# POWER_GATEWAY.net
KiCad netlist of a schematic drawn in Altium Designer
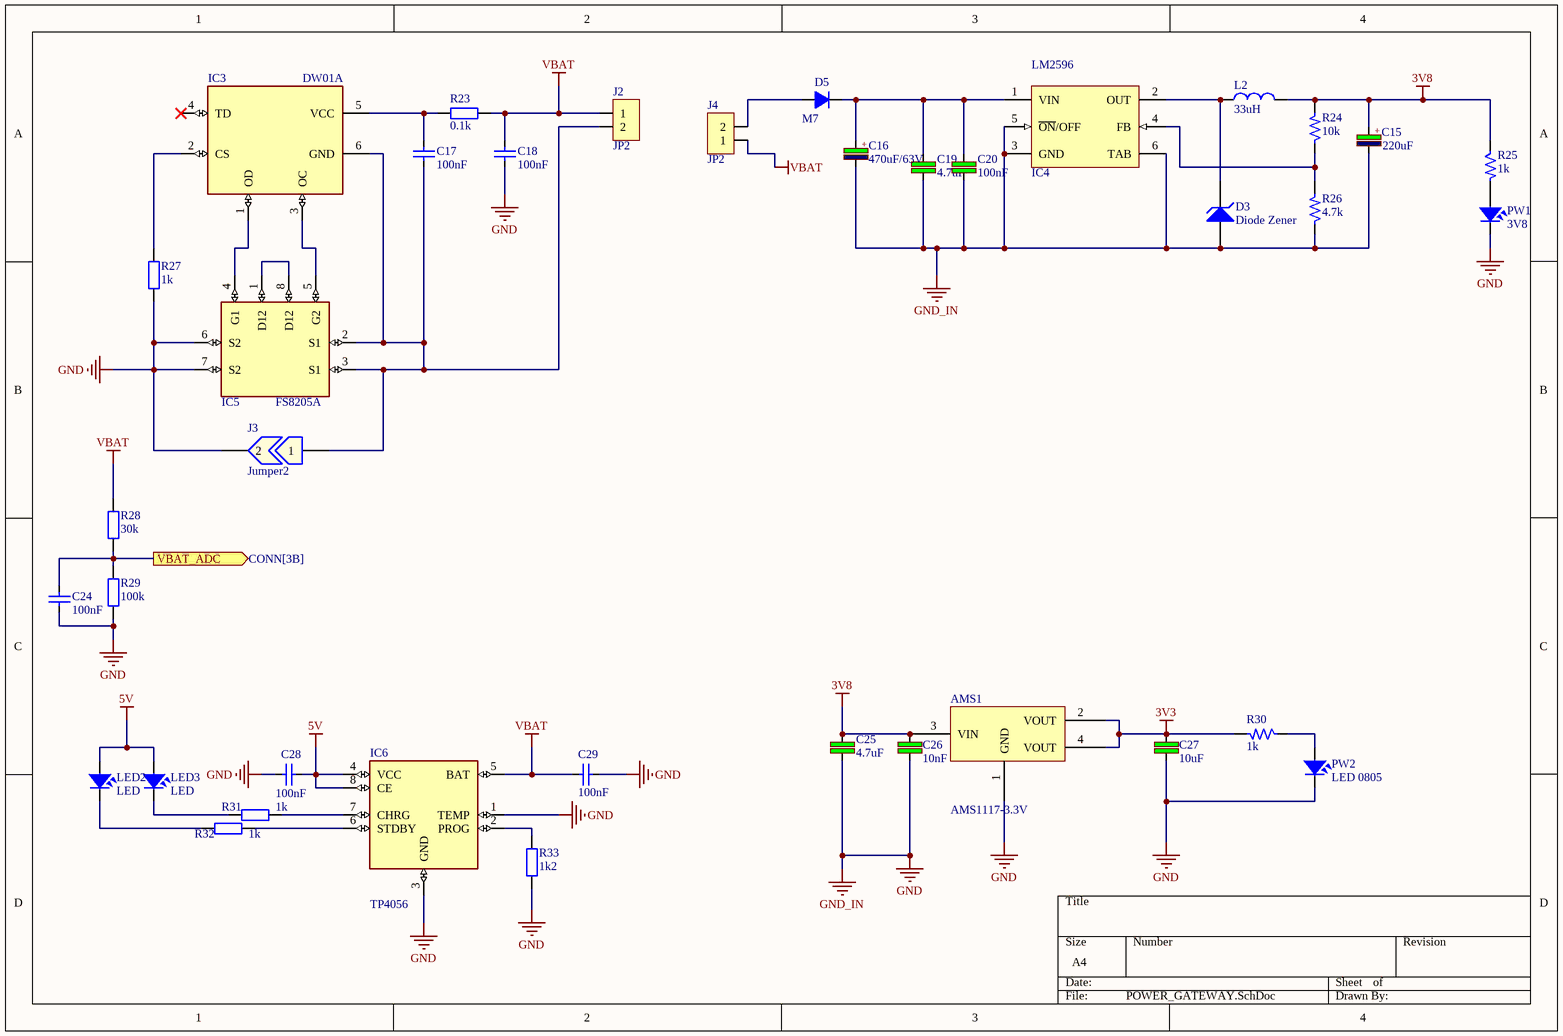
[diagram p0: POWER_GATEWAY.SchDoc]

(export (version "E")
  (design (tool "Eeschema 10.0.6"))
  (components
    (comp (ref "AMS1")
      (value "AMS1117-3.3V")
      (footprint "SOT223")
      (description "Dán")
      (libsource (lib "IC") (part "AMS1117 SMD"))
    )
    (comp (ref "C15")
      (value "220uF")
      (footprint "CAP_TANTALUM_3216")
      (description "220µF Molded Tantalum Polymer Capacitor 16V 2917 (7343 Metric) 40mOhm @ 100kHz")
      (fields
        (field (name "MANUFACTURER") "AVX Corporation")
        (field (name "PART NUMBER") "TCME227M016R0040E")
      )
      (libsource (lib "Anh_Trung") (part "CP5"))
    )
    (comp (ref "C16")
      (value "470uF/63V")
      (footprint "CAP-ALU-SMD-C")
      (description "Cap 470uF/63V")
      (libsource (lib "Main") (part "CP3"))
    )
    (comp (ref "C17")
      (value "100nF")
      (footprint "CAP_0805")
      (description "Capacitor")
      (fields (field (name "PUBLISHER") "Altium Limited"))
      (libsource (lib "My Library") (part "CapSMD"))
    )
    (comp (ref "C18")
      (value "100nF")
      (footprint "CAP_0805")
      (description "Capacitor")
      (fields (field (name "PUBLISHER") "Altium Limited"))
      (libsource (lib "My Library") (part "CapSMD"))
    )
    (comp (ref "C19")
      (value "4.7uF")
      (footprint "C-0805")
      (description "4.7µF ±10% 35V Ceramic Capacitor X5R 0805 (2012 Metric)")
      (fields
        (field (name "MANUFACTURER") "Samsung Electro-Mechanics")
        (field (name "PART NUMBER") "CL21A475KLCLQNC")
      )
      (libsource (lib "Anh_Trung") (part "C"))
    )
    (comp (ref "C20")
      (value "100nF")
      (footprint "C-0805")
      (description "4.7µF ±10% 35V Ceramic Capacitor X5R 0805 (2012 Metric)")
      (fields
        (field (name "MANUFACTURER") "Samsung Electro-Mechanics")
        (field (name "PART NUMBER") "CL21A475KLCLQNC")
      )
      (libsource (lib "Anh_Trung") (part "C"))
    )
    (comp (ref "C24")
      (value "100nF")
      (footprint "CAP_0805")
      (description "Capacitor")
      (fields (field (name "PUBLISHER") "Altium Limited"))
      (libsource (lib "My Library") (part "CapSMD"))
    )
    (comp (ref "C25")
      (value "4.7uF")
      (footprint "C-0805")
      (description "4.7µF ±10% 35V Ceramic Capacitor X5R 0805 (2012 Metric)")
      (fields
        (field (name "MANUFACTURER") "Samsung Electro-Mechanics")
        (field (name "PART NUMBER") "CL21A475KLCLQNC")
      )
      (libsource (lib "Anh_Trung") (part "C"))
    )
    (comp (ref "C26")
      (value "10nF")
      (footprint "C-0805")
      (description "Cap SMD")
      (fields
        (field (name "MANUFACTURER") "Samsung Electro-Mechanics")
        (field (name "PART NUMBER") "CL21A106KPFNNNG")
      )
      (libsource (lib "") (part "C_1"))
    )
    (comp (ref "C27")
      (value "10uF")
      (footprint "C-0805")
      (description "Cap SMD")
      (fields
        (field (name "MANUFACTURER") "Samsung Electro-Mechanics")
        (field (name "PART NUMBER") "CL21A106KPFNNNG")
      )
      (libsource (lib "") (part "C_1"))
    )
    (comp (ref "C28")
      (value "100nF")
      (footprint "CAP_0805")
      (description "Capacitor")
      (fields (field (name "PUBLISHER") "Altium Limited"))
      (libsource (lib "My Library") (part "CapSMD"))
    )
    (comp (ref "C29")
      (value "100nF")
      (footprint "CAP_0805")
      (description "Capacitor")
      (fields (field (name "PUBLISHER") "Altium Limited"))
      (libsource (lib "My Library") (part "CapSMD"))
    )
    (comp (ref "D3")
      (value "Diode Zener")
      (footprint "DIODE_ZENER_SMD")
      (description "Zener Diode")
      (fields (field (name "PUBLISHER") "Altium Limited"))
      (libsource (lib "My Library 2") (part "Diode Zener"))
    )
    (comp (ref "D5")
      (value "M7")
      (footprint "SMA")
      (description "Diode 1A")
      (libsource (lib "Main") (part "D1A"))
    )
    (comp (ref "IC3")
      (value "DW01A")
      (footprint "SOT23-6")
      (description "One Cell Lithium-ion/Polymer Battery Protection IC")
      (libsource (lib "My Library") (part "DW01A"))
    )
    (comp (ref "IC4")
      (value "LM2596")
      (footprint "TO-263")
      (description "LM2576")
      (libsource (lib "Main") (part "LM2576"))
    )
    (comp (ref "IC5") (value "FS8205A") (footprint "FS8205A") (libsource (lib "My Library") (part "FS8205A")))
    (comp (ref "IC6")
      (value "TP4056")
      (footprint "TP4056")
      (description "Complete single cell Li-Ion battery with a constant current / constant voltage linear charger")
      (libsource (lib "My Library") (part "TP4056"))
    )
    (comp (ref "J2")
      (value "JP2")
      (footprint "KF2-5.08")
      (description "WR-PHD 2.54 mm Angled Socket Header")
      (fields
        (field (name "MANUFACTURER") "Würth Elektronik eiSos GmbH")
        (field (name "PARTNO") "613002143121")
        (field (name "CREATED BY") "Karrer Zheng")
      )
      (libsource (lib "My Library") (part "JP2"))
    )
    (comp (ref "J3")
      (value "Jumper2")
      (footprint "JUMPER2")
      (description "Jumper, 2-Pin")
      (libsource (lib "My Library") (part "Jumper2"))
    )
    (comp (ref "J4")
      (value "JP2")
      (footprint "KF2-5.08")
      (description "WR-PHD 2.54 mm Angled Socket Header")
      (fields
        (field (name "MANUFACTURER") "Würth Elektronik eiSos GmbH")
        (field (name "PARTNO") "613002143121")
        (field (name "CREATED BY") "Karrer Zheng")
      )
      (libsource (lib "") (part "JP2_1"))
    )
    (comp (ref "L2")
      (value "33uH")
      (footprint "Inductor_SMD")
      (description "22µH Shielded Inductor 1.65A 96mOhm Max Nonstandard")
      (fields (field (name "MANUFACTURER") "Bourns Inc.") (field (name "PART NUMBER") "SRR0745A-220M"))
      (libsource (lib "Main") (part "L1"))
    )
    (comp (ref "LED2")
      (value "LED")
      (footprint "LED-0805-Blue")
      (description "LED Single colour Green and Red")
      (libsource (lib "My Library") (part "LED"))
    )
    (comp (ref "LED3")
      (value "LED")
      (footprint "LED-0805-Blue")
      (description "LED Single colour Green and Red")
      (libsource (lib "My Library") (part "LED"))
    )
    (comp (ref "PW1")
      (value "3V8")
      (footprint "LED-0805-Blue")
      (description "LED RED DIFFUSED 0805 SMD")
      (fields
        (field (name "MANUFACTURER") "OSRAM Opto Semiconductors Inc.")
        (field (name "PART NUMBER") "LS R976-NR-1")
      )
      (libsource (lib "Anh_Trung") (part "LED"))
    )
    (comp (ref "PW2")
      (value "LED 0805")
      (footprint "LED-0805-Blue")
      (description "LED RED DIFFUSED 0805 SMD")
      (fields
        (field (name "MANUFACTURER") "OSRAM Opto Semiconductors Inc.")
        (field (name "PART NUMBER") "LS R976-NR-1")
      )
      (libsource (lib "Main") (part "LED"))
    )
    (comp (ref "R23")
      (value "0.1k")
      (footprint "RES-SMD-0805")
      (description "Resistor SMD")
      (fields
        (field (name "MANUFACTURER") "Generic Components")
        (field (name "PUBLISHER") "Altium Hobart Technology Centre")
      )
      (libsource (lib "My Library") (part "Resistor - SMD"))
    )
    (comp (ref "R24")
      (value "10k")
      (footprint "R-0805")
      (description "RES SMD 10K OHM 1% 1/8W 0805")
      (fields (field (name "MANUFACTURER") "Yageo") (field (name "PART NUMBER") "RC0805FR-0710KL"))
      (libsource (lib "Anh_Trung") (part "R"))
    )
    (comp (ref "R25")
      (value "1k")
      (footprint "R-0805")
      (description "Resistor 1/4W")
      (fields (field (name "MANUFACTURER") "Yageo") (field (name "PART NUMBER") "RC0805FR-071KL"))
      (libsource (lib "Anh_Trung") (part "R"))
    )
    (comp (ref "R26")
      (value "4.7k")
      (footprint "R-0805")
      (description "RES SMD 3.3K OHM 1% 1/8W 0805")
      (fields (field (name "MANUFACTURER") "Yageo") (field (name "PART NUMBER") "RC0805FR-073K3L"))
      (libsource (lib "Anh_Trung") (part "R"))
    )
    (comp (ref "R27")
      (value "1k")
      (footprint "RES-SMD-0805")
      (description "Resistor SMD")
      (fields
        (field (name "MANUFACTURER") "Generic Components")
        (field (name "PUBLISHER") "Altium Hobart Technology Centre")
      )
      (libsource (lib "My Library") (part "Resistor - SMD"))
    )
    (comp (ref "R28")
      (value "30k")
      (footprint "RES-SMD-0805")
      (description "Resistor SMD")
      (fields
        (field (name "MANUFACTURER") "Generic Components")
        (field (name "PUBLISHER") "Altium Hobart Technology Centre")
      )
      (libsource (lib "My Library") (part "Resistor - SMD"))
    )
    (comp (ref "R29")
      (value "100k")
      (footprint "RES-SMD-0805")
      (description "Resistor SMD")
      (fields
        (field (name "MANUFACTURER") "Generic Components")
        (field (name "PUBLISHER") "Altium Hobart Technology Centre")
      )
      (libsource (lib "My Library") (part "Resistor - SMD"))
    )
    (comp (ref "R30")
      (value "1k")
      (footprint "R-0805")
      (description "Resistor 1/4W")
      (fields (field (name "MANUFACTURER") "Yageo") (field (name "PART NUMBER") "RC0805FR-071KL"))
      (libsource (lib "Anh_Trung") (part "R"))
    )
    (comp (ref "R31")
      (value "1k")
      (footprint "RES-SMD-0805")
      (description "Resistor SMD")
      (fields
        (field (name "MANUFACTURER") "Generic Components")
        (field (name "PUBLISHER") "Altium Hobart Technology Centre")
      )
      (libsource (lib "My Library") (part "Resistor - SMD"))
    )
    (comp (ref "R32")
      (value "1k")
      (footprint "RES-SMD-0805")
      (description "Resistor SMD")
      (fields
        (field (name "MANUFACTURER") "Generic Components")
        (field (name "PUBLISHER") "Altium Hobart Technology Centre")
      )
      (libsource (lib "My Library") (part "Resistor - SMD"))
    )
    (comp (ref "R33")
      (value "1k2")
      (footprint "RES-SMD-0805")
      (description "Resistor SMD")
      (fields
        (field (name "MANUFACTURER") "Generic Components")
        (field (name "PUBLISHER") "Altium Hobart Technology Centre")
      )
      (libsource (lib "My Library") (part "Resistor - SMD"))
    )
  )
  (nets
    (net (code "1") (name "/VBAT_ADC") (class "Default")
      (node (ref "C24") (pin "2") (pinfunction "2_2") (pintype "passive"))
      (node (ref "R28") (pin "1") (pinfunction "1_1") (pintype "passive"))
      (node (ref "R29") (pin "2") (pinfunction "2_2") (pintype "passive"))
    )
    (net (code "2") (name "3V3") (class "Default")
      (node (ref "AMS1") (pin "2") (pinfunction "VOUT_2") (pintype "passive"))
      (node (ref "AMS1") (pin "4") (pinfunction "VOUT_4") (pintype "passive"))
      (node (ref "C27") (pin "1") (pinfunction "1_1") (pintype "passive"))
      (node (ref "R30") (pin "2") (pinfunction "2_2") (pintype "passive"))
    )
    (net (code "3") (name "3V8") (class "Default")
      (node (ref "AMS1") (pin "3") (pinfunction "VIN_3") (pintype "passive"))
      (node (ref "C15") (pin "1") (pinfunction "1_1") (pintype "passive"))
      (node (ref "C25") (pin "2") (pinfunction "2_2") (pintype "passive"))
      (node (ref "C26") (pin "1") (pinfunction "1_1") (pintype "passive"))
      (node (ref "L2") (pin "2") (pinfunction "2_2") (pintype "passive"))
      (node (ref "R24") (pin "2") (pinfunction "2_2") (pintype "passive"))
      (node (ref "R25") (pin "1") (pinfunction "1_1") (pintype "passive"))
    )
    (net (code "4") (name "5V") (class "Default")
      (node (ref "C28") (pin "1") (pinfunction "1_1") (pintype "passive"))
      (node (ref "IC6") (pin "4") (pinfunction "VCC_4") (pintype "bidirectional"))
      (node (ref "IC6") (pin "8") (pinfunction "CE_8") (pintype "bidirectional"))
      (node (ref "LED2") (pin "1") (pinfunction "1_1") (pintype "passive"))
      (node (ref "LED3") (pin "1") (pinfunction "1_1") (pintype "passive"))
    )
    (net (code "5") (name "GND") (class "Default")
      (node (ref "AMS1") (pin "1") (pinfunction "GND_1") (pintype "passive"))
      (node (ref "C15") (pin "2") (pinfunction "2_2") (pintype "passive"))
      (node (ref "C16") (pin "2") (pinfunction "2_2") (pintype "passive"))
      (node (ref "C18") (pin "1") (pinfunction "1_1") (pintype "passive"))
      (node (ref "C19") (pin "1") (pinfunction "1_1") (pintype "passive"))
      (node (ref "C20") (pin "1") (pinfunction "1_1") (pintype "passive"))
      (node (ref "C24") (pin "1") (pinfunction "1_1") (pintype "passive"))
      (node (ref "C25") (pin "1") (pinfunction "1_1") (pintype "passive"))
      (node (ref "C26") (pin "2") (pinfunction "2_2") (pintype "passive"))
      (node (ref "C27") (pin "2") (pinfunction "2_2") (pintype "passive"))
      (node (ref "C28") (pin "2") (pinfunction "2_2") (pintype "passive"))
      (node (ref "C29") (pin "1") (pinfunction "1_1") (pintype "passive"))
      (node (ref "D3") (pin "1") (pinfunction "A_1") (pintype "passive"))
      (node (ref "IC4") (pin "3") (pinfunction "GND_3") (pintype "power_in"))
      (node (ref "IC4") (pin "5") (pinfunction "~{ON}/OFF_5") (pintype "input"))
      (node (ref "IC4") (pin "6") (pinfunction "TAB_6") (pintype "power_in"))
      (node (ref "IC5") (pin "6") (pinfunction "S2_6") (pintype "bidirectional"))
      (node (ref "IC5") (pin "7") (pinfunction "S2_7") (pintype "bidirectional"))
      (node (ref "IC6") (pin "1") (pinfunction "TEMP_1") (pintype "bidirectional"))
      (node (ref "IC6") (pin "3") (pinfunction "GND_3") (pintype "bidirectional"))
      (node (ref "J3") (pin "2") (pinfunction "2_2") (pintype "passive"))
      (node (ref "PW1") (pin "2") (pinfunction "2_2") (pintype "passive"))
      (node (ref "PW2") (pin "2") (pinfunction "2_2") (pintype "passive"))
      (node (ref "R26") (pin "1") (pinfunction "1_1") (pintype "passive"))
      (node (ref "R27") (pin "2") (pinfunction "2_2") (pintype "passive"))
      (node (ref "R29") (pin "1") (pinfunction "1_1") (pintype "passive"))
      (node (ref "R33") (pin "2") (pinfunction "2_2") (pintype "passive"))
    )
    (net (code "6") (name "Net-(D3-K)") (class "Default")
      (node (ref "D3") (pin "2") (pinfunction "K_2") (pintype "passive"))
      (node (ref "IC4") (pin "2") (pinfunction "OUT_2") (pintype "power_in"))
      (node (ref "L2") (pin "1") (pinfunction "1_1") (pintype "passive"))
    )
    (net (code "7") (name "Net-(D5-A)") (class "Default")
      (node (ref "D5") (pin "1") (pinfunction "A_1") (pintype "passive"))
      (node (ref "J4") (pin "2") (pinfunction "2_2") (pintype "passive"))
    )
    (net (code "8") (name "Net-(D5-K)") (class "Default")
      (node (ref "C16") (pin "1") (pinfunction "1_1") (pintype "passive"))
      (node (ref "C19") (pin "2") (pinfunction "2_2") (pintype "passive"))
      (node (ref "C20") (pin "2") (pinfunction "2_2") (pintype "passive"))
      (node (ref "D5") (pin "2") (pinfunction "K_2") (pintype "passive"))
      (node (ref "IC4") (pin "1") (pinfunction "VIN_1") (pintype "power_in"))
    )
    (net (code "9") (name "Net-(IC3-CS)") (class "Default")
      (node (ref "IC3") (pin "2") (pinfunction "CS_2") (pintype "bidirectional"))
      (node (ref "R27") (pin "1") (pinfunction "1_1") (pintype "passive"))
    )
    (net (code "10") (name "Net-(IC3-GND)") (class "Default")
      (node (ref "C17") (pin "1") (pinfunction "1_1") (pintype "passive"))
      (node (ref "IC3") (pin "6") (pinfunction "GND_6") (pintype "power_in"))
      (node (ref "IC5") (pin "2") (pinfunction "S1_2") (pintype "bidirectional"))
      (node (ref "IC5") (pin "3") (pinfunction "S1_3") (pintype "bidirectional"))
      (node (ref "J2") (pin "2") (pinfunction "2_2") (pintype "passive"))
      (node (ref "J3") (pin "1") (pinfunction "1_1") (pintype "passive"))
    )
    (net (code "11") (name "Net-(IC3-OC)") (class "Default")
      (node (ref "IC3") (pin "3") (pinfunction "OC_3") (pintype "bidirectional"))
      (node (ref "IC5") (pin "5") (pinfunction "G2_5") (pintype "bidirectional"))
    )
    (net (code "12") (name "Net-(IC3-OD)") (class "Default")
      (node (ref "IC3") (pin "1") (pinfunction "OD_1") (pintype "bidirectional"))
      (node (ref "IC5") (pin "4") (pinfunction "G1_4") (pintype "bidirectional"))
    )
    (net (code "13") (name "Net-(IC3-VCC)") (class "Default")
      (node (ref "C17") (pin "2") (pinfunction "2_2") (pintype "passive"))
      (node (ref "IC3") (pin "5") (pinfunction "VCC_5") (pintype "power_in"))
      (node (ref "R23") (pin "1") (pinfunction "1_1") (pintype "passive"))
    )
    (net (code "14") (name "Net-(IC4-FB)") (class "Default")
      (node (ref "IC4") (pin "4") (pinfunction "FB_4") (pintype "input"))
      (node (ref "R24") (pin "1") (pinfunction "1_1") (pintype "passive"))
      (node (ref "R26") (pin "2") (pinfunction "2_2") (pintype "passive"))
    )
    (net (code "15") (name "Net-(IC5-D12-Pad1)") (class "Default")
      (node (ref "IC5") (pin "1") (pinfunction "D12_1") (pintype "bidirectional"))
      (node (ref "IC5") (pin "8") (pinfunction "D12_8") (pintype "bidirectional"))
    )
    (net (code "16") (name "Net-(IC6-CHRG)") (class "Default")
      (node (ref "IC6") (pin "7") (pinfunction "CHRG_7") (pintype "bidirectional"))
      (node (ref "R31") (pin "2") (pinfunction "2_2") (pintype "passive"))
    )
    (net (code "17") (name "Net-(IC6-PROG)") (class "Default")
      (node (ref "IC6") (pin "2") (pinfunction "PROG_2") (pintype "bidirectional"))
      (node (ref "R33") (pin "1") (pinfunction "1_1") (pintype "passive"))
    )
    (net (code "18") (name "Net-(IC6-STDBY)") (class "Default")
      (node (ref "IC6") (pin "6") (pinfunction "STDBY_6") (pintype "bidirectional"))
      (node (ref "R32") (pin "2") (pinfunction "2_2") (pintype "passive"))
    )
    (net (code "19") (name "Net-(LED2-Pad2)") (class "Default")
      (node (ref "LED2") (pin "2") (pinfunction "2_2") (pintype "passive"))
      (node (ref "R32") (pin "1") (pinfunction "1_1") (pintype "passive"))
    )
    (net (code "20") (name "Net-(LED3-Pad2)") (class "Default")
      (node (ref "LED3") (pin "2") (pinfunction "2_2") (pintype "passive"))
      (node (ref "R31") (pin "1") (pinfunction "1_1") (pintype "passive"))
    )
    (net (code "21") (name "Net-(PW1-Pad1)") (class "Default")
      (node (ref "PW1") (pin "1") (pinfunction "1_1") (pintype "passive"))
      (node (ref "R25") (pin "2") (pinfunction "2_2") (pintype "passive"))
    )
    (net (code "22") (name "Net-(PW2-Pad1)") (class "Default")
      (node (ref "PW2") (pin "1") (pinfunction "1_1") (pintype "passive"))
      (node (ref "R30") (pin "1") (pinfunction "1_1") (pintype "passive"))
    )
    (net (code "23") (name "VBAT") (class "Default")
      (node (ref "C18") (pin "2") (pinfunction "2_2") (pintype "passive"))
      (node (ref "C29") (pin "2") (pinfunction "2_2") (pintype "passive"))
      (node (ref "IC6") (pin "5") (pinfunction "BAT_5") (pintype "bidirectional"))
      (node (ref "J2") (pin "1") (pinfunction "1_1") (pintype "passive"))
      (node (ref "J4") (pin "1") (pinfunction "1_1") (pintype "passive"))
      (node (ref "R23") (pin "2") (pinfunction "2_2") (pintype "passive"))
      (node (ref "R28") (pin "2") (pinfunction "2_2") (pintype "passive"))
    )
    (net (code "24") (name "unconnected-(IC3-TD-Pad4)") (class "Default")
      (node (ref "IC3") (pin "4") (pinfunction "TD_4") (pintype "bidirectional+no_connect"))
    )
  )
)
